# esp-rev2.net
KiCad netlist of a schematic drawn in EAGLE
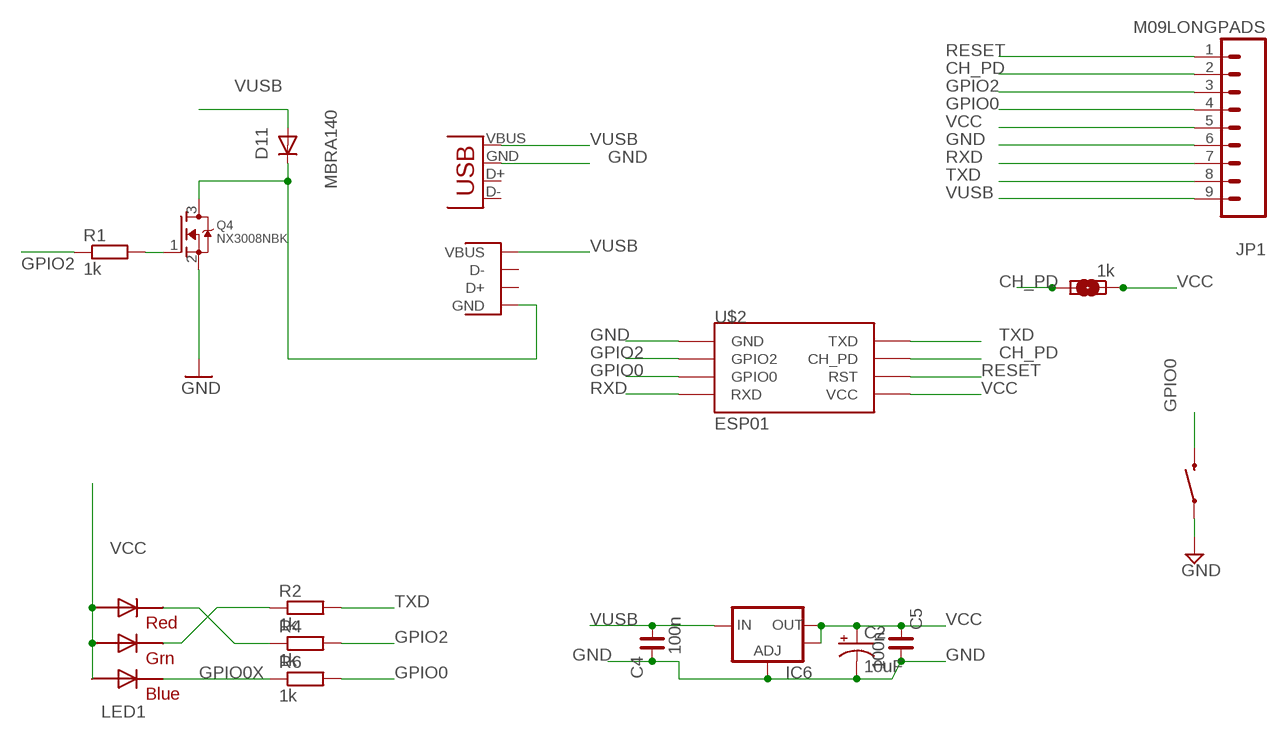
[diagram p0: schematic, sheet 1]

(export (version "E")
  (design (tool "Eeschema 10.0.6"))
  (components
    (comp (ref "C2")
      (value "10uF")
      (footprint "eagle-import:EIA3216")
      (libsource (lib "eagle-import") (part "CAP_POL1206"))
    )
    (comp (ref "C4")
      (value "100n")
      (footprint "eagle-import:C0603")
      (libsource (lib "eagle-import") (part "C_0603"))
    )
    (comp (ref "C5")
      (value "100n")
      (footprint "eagle-import:C0603")
      (libsource (lib "eagle-import") (part "C_0603"))
    )
    (comp (ref "D11")
      (value "MBRA140")
      (footprint "eagle-import:SOD-323")
      (libsource (lib "eagle-import") (part "DIODESOD"))
    )
    (comp (ref "IC6")
      (value "V_REG_LM1117SOT223")
      (footprint "eagle-import:SOT223")
      (libsource (lib "eagle-import") (part "V_REG_LM1117SOT223"))
    )
    (comp (ref "JP1")
      (value "M09LONGPADS")
      (footprint "eagle-import:1X09_LONGPADS")
      (libsource (lib "eagle-import") (part "M09LONGPADS"))
    )
    (comp (ref "LED1")
      (value "RGBLED5050")
      (footprint "eagle-import:RGBLED5050")
      (libsource (lib "eagle-import") (part "RGBLED5050"))
    )
    (comp (ref "PWR2")
      (value "SOLDERJUMPERTRACE")
      (footprint "eagle-import:SJ_2S-TRACE")
      (libsource (lib "eagle-import") (part "SOLDERJUMPERTRACE"))
    )
    (comp (ref "Q4")
      (value "NX3008NBK")
      (footprint "eagle-import:SOT23-WIDE")
      (libsource (lib "eagle-import") (part "MOSFET-NWIDE"))
    )
    (comp (ref "R1")
      (value "1k")
      (footprint "eagle-import:R0603")
      (libsource (lib "eagle-import") (part "R-EU_R0603"))
    )
    (comp (ref "R2")
      (value "1k")
      (footprint "eagle-import:R0603")
      (libsource (lib "eagle-import") (part "R-EU_R0603"))
    )
    (comp (ref "R4")
      (value "1k")
      (footprint "eagle-import:R0603")
      (libsource (lib "eagle-import") (part "R-EU_R0603"))
    )
    (comp (ref "R6")
      (value "1k")
      (footprint "eagle-import:R0603")
      (libsource (lib "eagle-import") (part "R-EU_R0603"))
    )
    (comp (ref "R8")
      (value "1k")
      (footprint "eagle-import:R0603")
      (libsource (lib "eagle-import") (part "R-EU_R0603"))
    )
    (comp (ref "RESET1")
      (value "SWITCH-MOMENTARY-2-SMD-1101NE")
      (footprint "eagle-import:TACTILE-SWITCH-1101NE")
      (libsource (lib "eagle-import") (part "SWITCH-MOMENTARY-2-SMD-1101NE"))
    )
    (comp (ref "U$2")
      (value "ESP01")
      (footprint "eagle-import:ESP01")
      (libsource (lib "eagle-import") (part "ESP01"))
    )
    (comp (ref "X1")
      (value "USB-A-H")
      (footprint "eagle-import:USB-A-H")
      (libsource (lib "eagle-import") (part "USB-A-H"))
    )
    (comp (ref "X3")
      (value "USB-A-H")
      (footprint "eagle-import:USB-A-H")
      (libsource (lib "eagle-import") (part "SparkFun_USB-A-H"))
    )
  )
  (nets
    (net (code "1") (name "/CH_PD") (class "Default")
      (node (ref "JP1") (pin "2") (pinfunction "2_2") (pintype "passive"))
      (node (ref "PWR2") (pin "1") (pinfunction "1_1") (pintype "passive"))
      (node (ref "R8") (pin "2") (pinfunction "2_2") (pintype "passive"))
      (node (ref "U$2") (pin "CH_PD") (pinfunction "CH_PD_CH_PD") (pintype "bidirectional"))
    )
    (net (code "2") (name "/GPIO0") (class "Default")
      (node (ref "JP1") (pin "4") (pinfunction "4_4") (pintype "passive"))
      (node (ref "R6") (pin "2") (pinfunction "2_2") (pintype "passive"))
      (node (ref "RESET1") (pin "P$2") (pinfunction "2_P$2") (pintype "passive"))
      (node (ref "U$2") (pin "GPIO0") (pinfunction "GPIO0_GPIO0") (pintype "bidirectional"))
    )
    (net (code "3") (name "/GPIO0X") (class "Default")
      (node (ref "LED1") (pin "4") (pinfunction "BLUE_C_4") (pintype "bidirectional"))
      (node (ref "R6") (pin "1") (pinfunction "1_1") (pintype "passive"))
    )
    (net (code "4") (name "/GPIO2") (class "Default")
      (node (ref "JP1") (pin "3") (pinfunction "3_3") (pintype "passive"))
      (node (ref "R1") (pin "1") (pinfunction "1_1") (pintype "passive"))
      (node (ref "R4") (pin "2") (pinfunction "2_2") (pintype "passive"))
      (node (ref "U$2") (pin "GPIO2") (pinfunction "GPIO2_GPIO2") (pintype "bidirectional"))
    )
    (net (code "5") (name "/RESET") (class "Default")
      (node (ref "JP1") (pin "1") (pinfunction "1_1") (pintype "passive"))
      (node (ref "U$2") (pin "RST") (pinfunction "RST_RST") (pintype "bidirectional"))
    )
    (net (code "6") (name "/RXD") (class "Default")
      (node (ref "JP1") (pin "7") (pinfunction "7_7") (pintype "passive"))
      (node (ref "U$2") (pin "RX") (pinfunction "RXD_RX") (pintype "bidirectional"))
    )
    (net (code "7") (name "/TXD") (class "Default")
      (node (ref "JP1") (pin "8") (pinfunction "8_8") (pintype "passive"))
      (node (ref "R2") (pin "2") (pinfunction "2_2") (pintype "passive"))
      (node (ref "U$2") (pin "TX") (pinfunction "TXD_TX") (pintype "bidirectional"))
    )
    (net (code "8") (name "/VCC") (class "Default")
      (node (ref "C2") (pin "A") (pinfunction "+_A") (pintype "passive"))
      (node (ref "C5") (pin "2") (pinfunction "2_2") (pintype "passive"))
      (node (ref "IC6") (pin "2") (pinfunction "OUT_2") (pintype "output"))
      (node (ref "IC6") (pin "4") (pinfunction "OUT_4") (pintype "output"))
      (node (ref "JP1") (pin "5") (pinfunction "5_5") (pintype "passive"))
      (node (ref "LED1") (pin "1") (pinfunction "GREEN_A_1") (pintype "bidirectional"))
      (node (ref "LED1") (pin "2") (pinfunction "RED_A_2") (pintype "bidirectional"))
      (node (ref "LED1") (pin "3") (pinfunction "BLUE_A_3") (pintype "bidirectional"))
      (node (ref "PWR2") (pin "2") (pinfunction "2_2") (pintype "passive"))
      (node (ref "R8") (pin "1") (pinfunction "1_1") (pintype "passive"))
      (node (ref "U$2") (pin "VCC") (pinfunction "VCC_VCC") (pintype "bidirectional"))
    )
    (net (code "9") (name "/VUSB") (class "Default")
      (node (ref "C4") (pin "1") (pinfunction "1_1") (pintype "passive"))
      (node (ref "D11") (pin "2") (pinfunction "A_2") (pintype "passive"))
      (node (ref "IC6") (pin "3") (pinfunction "IN_3") (pintype "input"))
      (node (ref "JP1") (pin "9") (pinfunction "9_9") (pintype "passive"))
      (node (ref "X1") (pin "VBUS") (pinfunction "VBUS_VBUS") (pintype "bidirectional"))
      (node (ref "X3") (pin "VBUS") (pinfunction "GND_VBUS") (pintype "bidirectional"))
    )
    (net (code "10") (name "GND") (class "Default")
      (node (ref "C2") (pin "C") (pinfunction "-_C") (pintype "passive"))
      (node (ref "C4") (pin "2") (pinfunction "2_2") (pintype "passive"))
      (node (ref "C5") (pin "1") (pinfunction "1_1") (pintype "passive"))
      (node (ref "IC6") (pin "1") (pinfunction "ADJ_1") (pintype "input"))
      (node (ref "JP1") (pin "6") (pinfunction "6_6") (pintype "passive"))
      (node (ref "Q4") (pin "2") (pinfunction "S_2") (pintype "bidirectional"))
      (node (ref "RESET1") (pin "P$1") (pinfunction "1_P$1") (pintype "passive"))
      (node (ref "U$2") (pin "GND") (pinfunction "GND_GND") (pintype "bidirectional"))
      (node (ref "X3") (pin "GND") (pinfunction "VBUS_GND") (pintype "bidirectional"))
    )
    (net (code "11") (name "Net-(D11-C)") (class "Default")
      (node (ref "D11") (pin "1") (pinfunction "C_1") (pintype "passive"))
      (node (ref "Q4") (pin "3") (pinfunction "D_3") (pintype "bidirectional"))
      (node (ref "X1") (pin "GND") (pinfunction "GND_GND") (pintype "bidirectional"))
    )
    (net (code "12") (name "Net-(LED1-GREEN_C)") (class "Default")
      (node (ref "LED1") (pin "6") (pinfunction "GREEN_C_6") (pintype "bidirectional"))
      (node (ref "R2") (pin "1") (pinfunction "1_1") (pintype "passive"))
    )
    (net (code "13") (name "Net-(LED1-RED_C)") (class "Default")
      (node (ref "LED1") (pin "5") (pinfunction "RED_C_5") (pintype "bidirectional"))
      (node (ref "R4") (pin "1") (pinfunction "1_1") (pintype "passive"))
    )
    (net (code "14") (name "Net-(Q4-G)") (class "Default")
      (node (ref "Q4") (pin "1") (pinfunction "G_1") (pintype "bidirectional"))
      (node (ref "R1") (pin "2") (pinfunction "2_2") (pintype "passive"))
    )
    (net (code "15") (name "unconnected-(X1-PadD+)") (class "Default")
      (node (ref "X1") (pin "D+") (pinfunction "D+_D+") (pintype "bidirectional"))
    )
    (net (code "16") (name "unconnected-(X1-PadD-)") (class "Default")
      (node (ref "X1") (pin "D-") (pinfunction "D-_D-") (pintype "bidirectional"))
    )
    (net (code "17") (name "unconnected-(X3-D+-PadD-)") (class "Default")
      (node (ref "X3") (pin "D-") (pinfunction "D+_D-") (pintype "bidirectional"))
    )
    (net (code "18") (name "unconnected-(X3-D--PadD+)") (class "Default")
      (node (ref "X3") (pin "D+") (pinfunction "D-_D+") (pintype "bidirectional"))
    )
  )
)
